# Linkwitz_mod.net
KiCad netlist of a schematic drawn in EAGLE
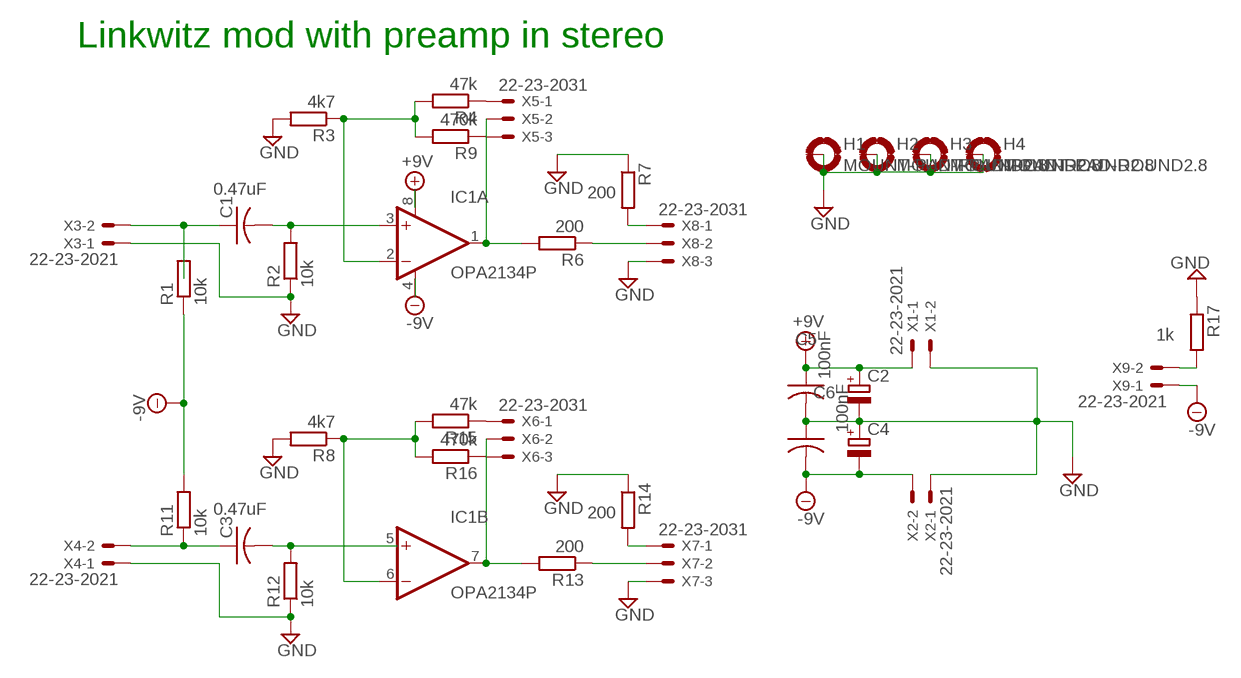
[diagram p0: schematic, sheet 1]

(export (version "E")
  (design (tool "Eeschema 10.0.6"))
  (components
    (comp (ref "C1")
      (value "0.47uF")
      (footprint "eagle-import:C050-030X075")
      (libsource (lib "eagle-import") (part "C-US050-030X075"))
    )
    (comp (ref "C2")
      (value "CPOL-EUE2,5-6E")
      (footprint "eagle-import:E2,5-6E")
      (libsource (lib "eagle-import") (part "CPOL-EUE2,5-6E"))
    )
    (comp (ref "C3")
      (value "0.47uF")
      (footprint "eagle-import:C050-030X075")
      (libsource (lib "eagle-import") (part "C-US050-030X075"))
    )
    (comp (ref "C4")
      (value "CPOL-EUE2,5-6E")
      (footprint "eagle-import:E2,5-6E")
      (libsource (lib "eagle-import") (part "CPOL-EUE2,5-6E"))
    )
    (comp (ref "C5")
      (value "100nF")
      (footprint "eagle-import:C050-030X075")
      (libsource (lib "eagle-import") (part "C-US050-030X075"))
    )
    (comp (ref "C6")
      (value "100nF")
      (footprint "eagle-import:C050-030X075")
      (libsource (lib "eagle-import") (part "C-US050-030X075"))
    )
    (comp (ref "H1")
      (value "MOUNT-PAD-ROUND2.8")
      (footprint "eagle-import:2,8-PAD")
      (libsource (lib "eagle-import") (part "MOUNT-PAD-ROUND2.8"))
    )
    (comp (ref "H2")
      (value "MOUNT-PAD-ROUND2.8")
      (footprint "eagle-import:2,8-PAD")
      (libsource (lib "eagle-import") (part "MOUNT-PAD-ROUND2.8"))
    )
    (comp (ref "H3")
      (value "MOUNT-PAD-ROUND2.8")
      (footprint "eagle-import:2,8-PAD")
      (libsource (lib "eagle-import") (part "MOUNT-PAD-ROUND2.8"))
    )
    (comp (ref "H4")
      (value "MOUNT-PAD-ROUND2.8")
      (footprint "eagle-import:2,8-PAD")
      (libsource (lib "eagle-import") (part "MOUNT-PAD-ROUND2.8"))
    )
    (comp (ref "IC1")
      (value "OPA2134P")
      (footprint "eagle-import:DIL08")
      (fields (field (name "MF") "TEXAS INSTRUMENTS") (field (name "MPN") "OPA2134PA"))
      (libsource (lib "eagle-import") (part "OPA2134P"))
    )
    (comp (ref "R1")
      (value "10k")
      (footprint "eagle-import:0309_10")
      (libsource (lib "eagle-import") (part "R-EU_0309/10"))
    )
    (comp (ref "R2")
      (value "10k")
      (footprint "eagle-import:0309_10")
      (libsource (lib "eagle-import") (part "R-EU_0309/10"))
    )
    (comp (ref "R3")
      (value "4k7")
      (footprint "eagle-import:0309_10")
      (libsource (lib "eagle-import") (part "R-EU_0309/10"))
    )
    (comp (ref "R4")
      (value "47k")
      (footprint "eagle-import:0309_10")
      (libsource (lib "eagle-import") (part "R-EU_0309/10"))
    )
    (comp (ref "R6")
      (value "200")
      (footprint "eagle-import:0309_10")
      (libsource (lib "eagle-import") (part "R-EU_0309/10"))
    )
    (comp (ref "R7")
      (value "200")
      (footprint "eagle-import:0309_10")
      (libsource (lib "eagle-import") (part "R-EU_0309/10"))
    )
    (comp (ref "R8")
      (value "4k7")
      (footprint "eagle-import:0309_10")
      (libsource (lib "eagle-import") (part "R-EU_0309/10"))
    )
    (comp (ref "R9")
      (value "470k")
      (footprint "eagle-import:0309_10")
      (libsource (lib "eagle-import") (part "R-EU_0309/10"))
    )
    (comp (ref "R11")
      (value "10k")
      (footprint "eagle-import:0309_10")
      (libsource (lib "eagle-import") (part "R-EU_0309/10"))
    )
    (comp (ref "R12")
      (value "10k")
      (footprint "eagle-import:0309_10")
      (libsource (lib "eagle-import") (part "R-EU_0309/10"))
    )
    (comp (ref "R13")
      (value "200")
      (footprint "eagle-import:0309_10")
      (libsource (lib "eagle-import") (part "R-EU_0309/10"))
    )
    (comp (ref "R14")
      (value "200")
      (footprint "eagle-import:0309_10")
      (libsource (lib "eagle-import") (part "R-EU_0309/10"))
    )
    (comp (ref "R15")
      (value "47k")
      (footprint "eagle-import:0309_10")
      (libsource (lib "eagle-import") (part "R-EU_0309/10"))
    )
    (comp (ref "R16")
      (value "470k")
      (footprint "eagle-import:0309_10")
      (libsource (lib "eagle-import") (part "R-EU_0309/10"))
    )
    (comp (ref "R17")
      (value "1k")
      (footprint "eagle-import:0309_10")
      (libsource (lib "eagle-import") (part "R-EU_0309/10"))
    )
    (comp (ref "X1")
      (value "22-23-2021")
      (footprint "eagle-import:22-23-2021")
      (fields
        (field (name "MF") "MOLEX")
        (field (name "MF_1") "MOLEX")
        (field (name "MPN") "22-23-2021")
        (field (name "OC_FARNELL") "1462926")
        (field (name "OC_NEWARK") "25C3832")
      )
      (libsource (lib "eagle-import") (part "22-23-2021"))
    )
    (comp (ref "X2")
      (value "22-23-2021")
      (footprint "eagle-import:22-23-2021")
      (fields
        (field (name "MF") "MOLEX")
        (field (name "MF_1") "MOLEX")
        (field (name "MPN") "22-23-2021")
        (field (name "OC_FARNELL") "1462926")
        (field (name "OC_NEWARK") "25C3832")
      )
      (libsource (lib "eagle-import") (part "22-23-2021"))
    )
    (comp (ref "X3")
      (value "22-23-2021")
      (footprint "eagle-import:22-23-2021")
      (fields (field (name "MF") "MOLEX"))
      (libsource (lib "eagle-import") (part "22-23-2021"))
    )
    (comp (ref "X4")
      (value "22-23-2021")
      (footprint "eagle-import:22-23-2021")
      (fields (field (name "MF") "MOLEX"))
      (libsource (lib "eagle-import") (part "22-23-2021"))
    )
    (comp (ref "X5")
      (value "22-23-2031")
      (footprint "eagle-import:22-23-2031")
      (fields (field (name "MF") "MOLEX"))
      (libsource (lib "eagle-import") (part "22-23-2031"))
    )
    (comp (ref "X6")
      (value "22-23-2031")
      (footprint "eagle-import:22-23-2031")
      (fields (field (name "MF") "MOLEX"))
      (libsource (lib "eagle-import") (part "22-23-2031"))
    )
    (comp (ref "X7")
      (value "22-23-2031")
      (footprint "eagle-import:22-23-2031")
      (fields (field (name "MF") "MOLEX"))
      (libsource (lib "eagle-import") (part "22-23-2031"))
    )
    (comp (ref "X8")
      (value "22-23-2031")
      (footprint "eagle-import:22-23-2031")
      (fields (field (name "MF") "MOLEX"))
      (libsource (lib "eagle-import") (part "22-23-2031"))
    )
    (comp (ref "X9")
      (value "22-23-2021")
      (footprint "eagle-import:22-23-2021")
      (fields
        (field (name "MF") "MOLEX")
        (field (name "MF_1") "MOLEX")
        (field (name "MPN") "22-23-2021")
        (field (name "OC_FARNELL") "1462926")
        (field (name "OC_NEWARK") "25C3832")
      )
      (libsource (lib "eagle-import") (part "22-23-2021"))
    )
  )
  (nets
    (net (code "1") (name "+9V") (class "Default")
      (node (ref "C2") (pin "+") (pinfunction "+_+") (pintype "passive"))
      (node (ref "C5") (pin "1") (pinfunction "1_1") (pintype "passive"))
      (node (ref "IC1") (pin "8") (pinfunction "V+_8") (pintype "power_in"))
      (node (ref "X1") (pin "1") (pinfunction "S_1") (pintype "passive"))
    )
    (net (code "2") (name "-9V") (class "Default")
      (node (ref "C4") (pin "-") (pinfunction "-_-") (pintype "passive"))
      (node (ref "C6") (pin "2") (pinfunction "2_2") (pintype "passive"))
      (node (ref "IC1") (pin "4") (pinfunction "V-_4") (pintype "power_in"))
      (node (ref "R1") (pin "1") (pinfunction "1_1") (pintype "passive"))
      (node (ref "R11") (pin "2") (pinfunction "2_2") (pintype "passive"))
      (node (ref "X2") (pin "2") (pinfunction "S_2") (pintype "passive"))
      (node (ref "X9") (pin "1") (pinfunction "S_1") (pintype "passive"))
    )
    (net (code "3") (name "GND") (class "Default")
      (node (ref "C2") (pin "-") (pinfunction "-_-") (pintype "passive"))
      (node (ref "C4") (pin "+") (pinfunction "+_+") (pintype "passive"))
      (node (ref "C5") (pin "2") (pinfunction "2_2") (pintype "passive"))
      (node (ref "C6") (pin "1") (pinfunction "1_1") (pintype "passive"))
      (node (ref "R12") (pin "1") (pinfunction "1_1") (pintype "passive"))
      (node (ref "R14") (pin "1") (pinfunction "1_1") (pintype "passive"))
      (node (ref "R17") (pin "1") (pinfunction "1_1") (pintype "passive"))
      (node (ref "R2") (pin "1") (pinfunction "1_1") (pintype "passive"))
      (node (ref "R3") (pin "2") (pinfunction "2_2") (pintype "passive"))
      (node (ref "R7") (pin "1") (pinfunction "1_1") (pintype "passive"))
      (node (ref "R8") (pin "2") (pinfunction "2_2") (pintype "passive"))
      (node (ref "X1") (pin "2") (pinfunction "S_2") (pintype "passive"))
      (node (ref "X2") (pin "1") (pinfunction "S_1") (pintype "passive"))
      (node (ref "X3") (pin "1") (pinfunction "S_1") (pintype "passive"))
      (node (ref "X4") (pin "1") (pinfunction "S_1") (pintype "passive"))
      (node (ref "X7") (pin "3") (pinfunction "S_3") (pintype "passive"))
      (node (ref "X8") (pin "3") (pinfunction "S_3") (pintype "passive"))
    )
    (net (code "4") (name "Net-(IC1A-+IN)") (class "Default")
      (node (ref "C1") (pin "2") (pinfunction "2_2") (pintype "passive"))
      (node (ref "IC1") (pin "3") (pinfunction "+IN_3") (pintype "input"))
      (node (ref "R2") (pin "2") (pinfunction "2_2") (pintype "passive"))
    )
    (net (code "5") (name "Net-(IC1A--IN)") (class "Default")
      (node (ref "IC1") (pin "2") (pinfunction "-IN_2") (pintype "input"))
      (node (ref "R3") (pin "1") (pinfunction "1_1") (pintype "passive"))
      (node (ref "R4") (pin "2") (pinfunction "2_2") (pintype "passive"))
      (node (ref "R9") (pin "2") (pinfunction "2_2") (pintype "passive"))
    )
    (net (code "6") (name "Net-(IC1A-OUT)") (class "Default")
      (node (ref "IC1") (pin "1") (pinfunction "OUT_1") (pintype "output"))
      (node (ref "R6") (pin "2") (pinfunction "2_2") (pintype "passive"))
      (node (ref "X5") (pin "2") (pinfunction "S_2") (pintype "passive"))
    )
    (net (code "7") (name "Net-(IC1B-+IN)") (class "Default")
      (node (ref "C3") (pin "2") (pinfunction "2_2") (pintype "passive"))
      (node (ref "IC1") (pin "5") (pinfunction "+IN_5") (pintype "input"))
      (node (ref "R12") (pin "2") (pinfunction "2_2") (pintype "passive"))
    )
    (net (code "8") (name "Net-(IC1B--IN)") (class "Default")
      (node (ref "IC1") (pin "6") (pinfunction "-IN_6") (pintype "input"))
      (node (ref "R15") (pin "2") (pinfunction "2_2") (pintype "passive"))
      (node (ref "R16") (pin "2") (pinfunction "2_2") (pintype "passive"))
      (node (ref "R8") (pin "1") (pinfunction "1_1") (pintype "passive"))
    )
    (net (code "9") (name "Net-(IC1B-OUT)") (class "Default")
      (node (ref "IC1") (pin "7") (pinfunction "OUT_7") (pintype "output"))
      (node (ref "R13") (pin "2") (pinfunction "2_2") (pintype "passive"))
      (node (ref "X6") (pin "2") (pinfunction "S_2") (pintype "passive"))
    )
    (net (code "10") (name "Net-(X3B-S)") (class "Default")
      (node (ref "C1") (pin "1") (pinfunction "1_1") (pintype "passive"))
      (node (ref "R1") (pin "2") (pinfunction "2_2") (pintype "passive"))
      (node (ref "X3") (pin "2") (pinfunction "S_2") (pintype "passive"))
    )
    (net (code "11") (name "Net-(X4B-S)") (class "Default")
      (node (ref "C3") (pin "1") (pinfunction "1_1") (pintype "passive"))
      (node (ref "R11") (pin "1") (pinfunction "1_1") (pintype "passive"))
      (node (ref "X4") (pin "2") (pinfunction "S_2") (pintype "passive"))
    )
    (net (code "12") (name "Net-(X5A-S)") (class "Default")
      (node (ref "R4") (pin "1") (pinfunction "1_1") (pintype "passive"))
      (node (ref "X5") (pin "1") (pinfunction "S_1") (pintype "passive"))
    )
    (net (code "13") (name "Net-(X5C-S)") (class "Default")
      (node (ref "R9") (pin "1") (pinfunction "1_1") (pintype "passive"))
      (node (ref "X5") (pin "3") (pinfunction "S_3") (pintype "passive"))
    )
    (net (code "14") (name "Net-(X6A-S)") (class "Default")
      (node (ref "R15") (pin "1") (pinfunction "1_1") (pintype "passive"))
      (node (ref "X6") (pin "1") (pinfunction "S_1") (pintype "passive"))
    )
    (net (code "15") (name "Net-(X6C-S)") (class "Default")
      (node (ref "R16") (pin "1") (pinfunction "1_1") (pintype "passive"))
      (node (ref "X6") (pin "3") (pinfunction "S_3") (pintype "passive"))
    )
    (net (code "16") (name "Net-(X7A-S)") (class "Default")
      (node (ref "R14") (pin "2") (pinfunction "2_2") (pintype "passive"))
      (node (ref "X7") (pin "1") (pinfunction "S_1") (pintype "passive"))
    )
    (net (code "17") (name "Net-(X7B-S)") (class "Default")
      (node (ref "R13") (pin "1") (pinfunction "1_1") (pintype "passive"))
      (node (ref "X7") (pin "2") (pinfunction "S_2") (pintype "passive"))
    )
    (net (code "18") (name "Net-(X8A-S)") (class "Default")
      (node (ref "R7") (pin "2") (pinfunction "2_2") (pintype "passive"))
      (node (ref "X8") (pin "1") (pinfunction "S_1") (pintype "passive"))
    )
    (net (code "19") (name "Net-(X8B-S)") (class "Default")
      (node (ref "R6") (pin "1") (pinfunction "1_1") (pintype "passive"))
      (node (ref "X8") (pin "2") (pinfunction "S_2") (pintype "passive"))
    )
    (net (code "20") (name "Net-(X9B-S)") (class "Default")
      (node (ref "R17") (pin "2") (pinfunction "2_2") (pintype "passive"))
      (node (ref "X9") (pin "2") (pinfunction "S_2") (pintype "passive"))
    )
    (net (code "21") (name "unconnected-(H1-MOUNT-PadB2,8)") (class "Default")
      (node (ref "H1") (pin "B2,8") (pinfunction "MOUNT_B2,8") (pintype "passive"))
    )
    (net (code "22") (name "unconnected-(H2-MOUNT-PadB2,8)") (class "Default")
      (node (ref "H2") (pin "B2,8") (pinfunction "MOUNT_B2,8") (pintype "passive"))
    )
    (net (code "23") (name "unconnected-(H3-MOUNT-PadB2,8)") (class "Default")
      (node (ref "H3") (pin "B2,8") (pinfunction "MOUNT_B2,8") (pintype "passive"))
    )
    (net (code "24") (name "unconnected-(H4-MOUNT-PadB2,8)") (class "Default")
      (node (ref "H4") (pin "B2,8") (pinfunction "MOUNT_B2,8") (pintype "passive"))
    )
  )
)
